# Genus_MainBoard_Lite-v_1_0.net
KiCad netlist of a schematic drawn in EAGLE
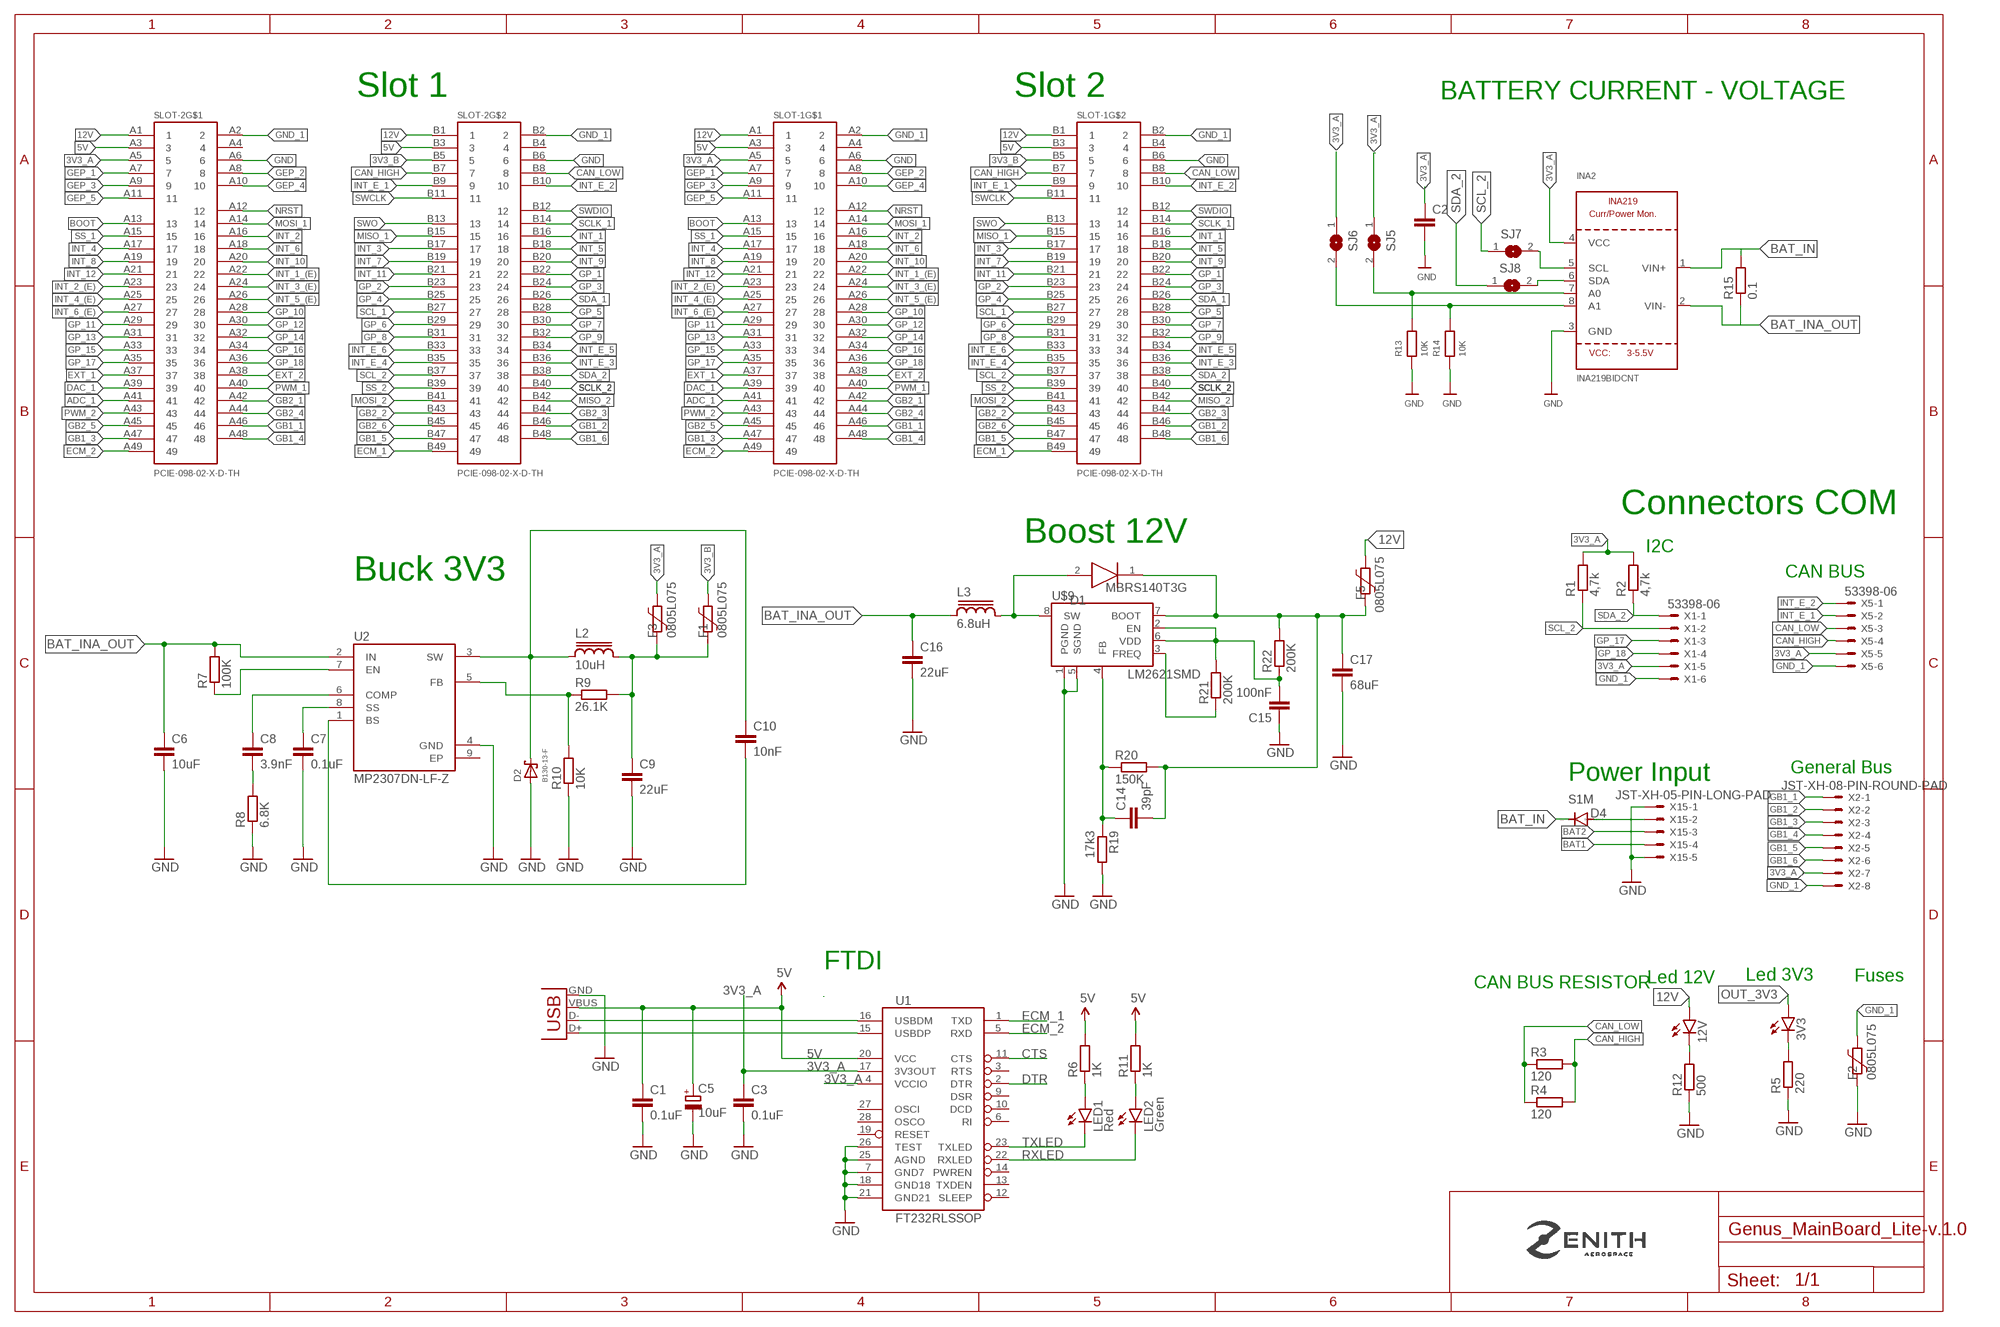
[diagram p0: schematic, sheet 1]

(export (version "E")
  (design (tool "Eeschema 10.0.6"))
  (components
    (comp (ref "3V3")
      (value "LEDCHIP-LED0805")
      (footprint "eagle-import:CHIP-LED0805")
      (libsource (lib "eagle-import") (part "LEDCHIP-LED0805"))
    )
    (comp (ref "12V")
      (value "LEDCHIP-LED0805")
      (footprint "eagle-import:CHIP-LED0805")
      (libsource (lib "eagle-import") (part "LEDCHIP-LED0805"))
    )
    (comp (ref "C1")
      (value "0.1uF")
      (footprint "eagle-import:C0805")
      (libsource (lib "eagle-import") (part "C-EUC0805"))
    )
    (comp (ref "C2")
      (value "C-EUC0805")
      (footprint "eagle-import:C0805")
      (libsource (lib "eagle-import") (part "C-EUC0805"))
    )
    (comp (ref "C3")
      (value "0.1uF")
      (footprint "eagle-import:C0805")
      (libsource (lib "eagle-import") (part "C-EUC0805"))
    )
    (comp (ref "C5")
      (value "10uF")
      (footprint "eagle-import:PANASONIC_B")
      (libsource (lib "eagle-import") (part "CPOL-EUB"))
    )
    (comp (ref "C6")
      (value "10uF")
      (footprint "eagle-import:C0805")
      (libsource (lib "eagle-import") (part "C-EUC0805"))
    )
    (comp (ref "C7")
      (value "0.1uF")
      (footprint "eagle-import:C0805")
      (libsource (lib "eagle-import") (part "C-EUC0805"))
    )
    (comp (ref "C8")
      (value "3.9nF")
      (footprint "eagle-import:C0805")
      (libsource (lib "eagle-import") (part "C-EUC0805"))
    )
    (comp (ref "C9")
      (value "22uF")
      (footprint "eagle-import:C0805")
      (libsource (lib "eagle-import") (part "C-EUC0805"))
    )
    (comp (ref "C10")
      (value "10nF")
      (footprint "eagle-import:C0805")
      (libsource (lib "eagle-import") (part "C-EUC0805"))
    )
    (comp (ref "C14")
      (value "39pF")
      (footprint "eagle-import:C0805")
      (libsource (lib "eagle-import") (part "C-EUC0805"))
    )
    (comp (ref "C15")
      (value "100nF")
      (footprint "eagle-import:C0805")
      (libsource (lib "eagle-import") (part "C-EUC0805"))
    )
    (comp (ref "C16")
      (value "22uF")
      (footprint "eagle-import:C1210")
      (libsource (lib "eagle-import") (part "C-EUC1210"))
    )
    (comp (ref "C17")
      (value "68uF")
      (footprint "eagle-import:C1210")
      (libsource (lib "eagle-import") (part "C-EUC1210"))
    )
    (comp (ref "D1")
      (value "MBRS140T3G")
      (footprint "eagle-import:DIOM5436X247N")
      (fields (field (name "RS_PART_NUMBER") "5452074P"))
      (libsource (lib "eagle-import") (part "MBRS140T3G"))
    )
    (comp (ref "D2")
      (value "B130-13-F")
      (footprint "eagle-import:SMA")
      (fields (field (name "MF") "Multicomp"))
      (libsource (lib "eagle-import") (part "B130-13-F"))
    )
    (comp (ref "D4")
      (value "S1M")
      (footprint "eagle-import:SMA")
      (libsource (lib "eagle-import") (part "S1M"))
    )
    (comp (ref "F1")
      (value "0805L075")
      (footprint "eagle-import:0805L")
      (fields (field (name "MF") "Littelfuse"))
      (libsource (lib "eagle-import") (part "?0805L075"))
    )
    (comp (ref "F2")
      (value "0805L075")
      (footprint "eagle-import:0805L")
      (fields (field (name "MF") "Littelfuse"))
      (libsource (lib "eagle-import") (part "?0805L075"))
    )
    (comp (ref "F3")
      (value "0805L075")
      (footprint "eagle-import:0805L")
      (fields (field (name "MF") "Littelfuse"))
      (libsource (lib "eagle-import") (part "?0805L075"))
    )
    (comp (ref "F5")
      (value "0805L075")
      (footprint "eagle-import:0805L")
      (fields (field (name "MF") "Littelfuse"))
      (libsource (lib "eagle-import") (part "?0805L075"))
    )
    (comp (ref "INA2")
      (value "INA219BIDCNT")
      (footprint "eagle-import:SOT23-8")
      (libsource (lib "eagle-import") (part "INA219"))
    )
    (comp (ref "L2")
      (value "10uH")
      (footprint "eagle-import:SRR1280")
      (libsource (lib "eagle-import") (part "SRR1280"))
    )
    (comp (ref "L3")
      (value "6.8uH")
      (footprint "eagle-import:SRR1280")
      (libsource (lib "eagle-import") (part "SRR1280"))
    )
    (comp (ref "LED1")
      (value "Red")
      (footprint "eagle-import:CHIPLED_0805")
      (libsource (lib "eagle-import") (part "LEDCHIPLED_0805"))
    )
    (comp (ref "LED2")
      (value "Green")
      (footprint "eagle-import:CHIPLED_0805")
      (libsource (lib "eagle-import") (part "LEDCHIPLED_0805"))
    )
    (comp (ref "R1")
      (value "4,7k")
      (footprint "eagle-import:R0805")
      (libsource (lib "eagle-import") (part "R-EU_R0805"))
    )
    (comp (ref "R2")
      (value "4,7k")
      (footprint "eagle-import:R0805")
      (libsource (lib "eagle-import") (part "R-EU_R0805"))
    )
    (comp (ref "R3")
      (value "120")
      (footprint "eagle-import:R0805")
      (libsource (lib "eagle-import") (part "R-EU_R0805"))
    )
    (comp (ref "R4")
      (value "120")
      (footprint "eagle-import:R0805")
      (libsource (lib "eagle-import") (part "R-EU_R0805"))
    )
    (comp (ref "R5")
      (value "220")
      (footprint "eagle-import:R0805")
      (libsource (lib "eagle-import") (part "R-EU_R0805"))
    )
    (comp (ref "R6")
      (value "1K")
      (footprint "eagle-import:R0805")
      (libsource (lib "eagle-import") (part "R-EU_R0805"))
    )
    (comp (ref "R7")
      (value "100K")
      (footprint "eagle-import:R0805")
      (libsource (lib "eagle-import") (part "R-EU_R0805"))
    )
    (comp (ref "R8")
      (value "6.8K")
      (footprint "eagle-import:R0805")
      (libsource (lib "eagle-import") (part "R-EU_R0805"))
    )
    (comp (ref "R9")
      (value "26.1K")
      (footprint "eagle-import:R0805")
      (libsource (lib "eagle-import") (part "R-EU_R0805"))
    )
    (comp (ref "R10")
      (value "10K")
      (footprint "eagle-import:R0805")
      (libsource (lib "eagle-import") (part "R-EU_R0805"))
    )
    (comp (ref "R11")
      (value "1K")
      (footprint "eagle-import:R0805")
      (libsource (lib "eagle-import") (part "R-EU_R0805"))
    )
    (comp (ref "R12")
      (value "500")
      (footprint "eagle-import:R0805")
      (libsource (lib "eagle-import") (part "R-EU_R0805"))
    )
    (comp (ref "R13")
      (value "10K")
      (footprint "eagle-import:R0805")
      (libsource (lib "eagle-import") (part "R-EU_R0805"))
    )
    (comp (ref "R14")
      (value "10K")
      (footprint "eagle-import:R0805")
      (libsource (lib "eagle-import") (part "R-EU_R0805"))
    )
    (comp (ref "R15")
      (value "0.1")
      (footprint "eagle-import:R2512")
      (libsource (lib "eagle-import") (part "R-EU_R2512"))
    )
    (comp (ref "R19")
      (value "17k3")
      (footprint "eagle-import:R0805")
      (libsource (lib "eagle-import") (part "R-EU_R0805"))
    )
    (comp (ref "R20")
      (value "150K")
      (footprint "eagle-import:R0805")
      (libsource (lib "eagle-import") (part "R-EU_R0805"))
    )
    (comp (ref "R21")
      (value "200K")
      (footprint "eagle-import:R0805")
      (libsource (lib "eagle-import") (part "R-EU_R0805"))
    )
    (comp (ref "R22")
      (value "200K")
      (footprint "eagle-import:R0805")
      (libsource (lib "eagle-import") (part "R-EU_R0805"))
    )
    (comp (ref "SJ5")
      (value "SOLDERJUMPERREFLOW_NOPASTE")
      (footprint "eagle-import:SOLDERJUMPER_REFLOW_NOPASTE")
      (libsource (lib "eagle-import") (part "SOLDERJUMPERREFLOW_NOPASTE"))
    )
    (comp (ref "SJ6")
      (value "SOLDERJUMPERREFLOW_NOPASTE")
      (footprint "eagle-import:SOLDERJUMPER_REFLOW_NOPASTE")
      (libsource (lib "eagle-import") (part "SOLDERJUMPERREFLOW_NOPASTE"))
    )
    (comp (ref "SJ7")
      (value "SOLDERJUMPERREFLOW_NOPASTE")
      (footprint "eagle-import:SOLDERJUMPER_REFLOW_NOPASTE")
      (libsource (lib "eagle-import") (part "SOLDERJUMPERREFLOW_NOPASTE"))
    )
    (comp (ref "SJ8")
      (value "SOLDERJUMPERREFLOW_NOPASTE")
      (footprint "eagle-import:SOLDERJUMPER_REFLOW_NOPASTE")
      (libsource (lib "eagle-import") (part "SOLDERJUMPERREFLOW_NOPASTE"))
    )
    (comp (ref "SLOT-1")
      (value "PCIE-098-02-X-D-TH")
      (footprint "eagle-import:PCIE-098-02-X-D-TH")
      (fields (field (name "MF") "Samtec") (field (name "MP") "PCIE-098-02-F-D-TH"))
      (libsource (lib "eagle-import") (part "PCIE-098-02-X-D-TH"))
    )
    (comp (ref "SLOT-2")
      (value "PCIE-098-02-X-D-TH")
      (footprint "eagle-import:PCIE-098-02-X-D-TH")
      (fields (field (name "MF") "Samtec") (field (name "MP") "PCIE-098-02-F-D-TH"))
      (libsource (lib "eagle-import") (part "PCIE-098-02-X-D-TH"))
    )
    (comp (ref "U$9")
      (value "LM2621SMD")
      (footprint "eagle-import:MSOP-8")
      (libsource (lib "eagle-import") (part "LM2621SMD"))
    )
    (comp (ref "U1")
      (value "FT232RLSSOP")
      (footprint "eagle-import:SSOP28DB")
      (libsource (lib "eagle-import") (part "FT232RLSSOP"))
    )
    (comp (ref "U2")
      (value "MP2307DN-LF-Z")
      (footprint "eagle-import:SOIC127P600X170-9N")
      (fields (field (name "MF") "Monolithic Power"))
      (libsource (lib "eagle-import") (part "MP2307DN-LF-Z"))
    )
    (comp (ref "X1")
      (value "53398-06")
      (footprint "eagle-import:53398-06")
      (fields (field (name "MF") "MOLEX"))
      (libsource (lib "eagle-import") (part "53?-06398"))
    )
    (comp (ref "X2")
      (value "JST-XH-08-PIN-ROUND-PAD")
      (footprint "eagle-import:JST-XH-08-PACKAGE-ROUND-PAD")
      (libsource (lib "eagle-import") (part "JST-XH-08-PIN-ROUND-PAD"))
    )
    (comp (ref "X3")
      (value "USB-SMD-NS")
      (footprint "eagle-import:USB-MINIB-NOSTOP")
      (libsource (lib "eagle-import") (part "USB-SMD-NS"))
    )
    (comp (ref "X5")
      (value "53398-06")
      (footprint "eagle-import:53398-06")
      (fields (field (name "MF") "MOLEX"))
      (libsource (lib "eagle-import") (part "53?-06398"))
    )
    (comp (ref "X15")
      (value "JST-XH-05-PIN-LONG-PAD")
      (footprint "eagle-import:JST-XH-05-PACKAGE-LONG-PAD")
      (libsource (lib "eagle-import") (part "JST-XH-05-PIN-LONG-PAD"))
    )
  )
  (nets
    (net (code "1") (name "/CTS") (class "Default")
      (node (ref "U1") (pin "11") (pinfunction "CTS_11") (pintype "input"))
    )
    (net (code "2") (name "/DTR") (class "Default")
      (node (ref "U1") (pin "2") (pinfunction "DTR_2") (pintype "output"))
    )
    (net (code "3") (name "/EP") (class "Default")
      (node (ref "U2") (pin "9") (pinfunction "EP_9") (pintype "power_in"))
    )
    (net (code "4") (name "/RXLED") (class "Default")
      (node (ref "LED2") (pin "C") (pinfunction "C_C") (pintype "passive"))
      (node (ref "U1") (pin "22") (pinfunction "RXLED_22") (pintype "input"))
    )
    (net (code "5") (name "/TXLED") (class "Default")
      (node (ref "LED1") (pin "C") (pinfunction "C_C") (pintype "passive"))
      (node (ref "U1") (pin "23") (pinfunction "TXLED_23") (pintype "input"))
    )
    (net (code "6") (name "3V3_A") (class "Default")
      (node (ref "C2") (pin "1") (pinfunction "1_1") (pintype "passive"))
      (node (ref "C3") (pin "1") (pinfunction "1_1") (pintype "passive"))
      (node (ref "F3") (pin "1") (pinfunction "1_1") (pintype "passive"))
      (node (ref "INA2") (pin "4") (pinfunction "VCC_4") (pintype "bidirectional"))
      (node (ref "R1") (pin "2") (pinfunction "2_2") (pintype "passive"))
      (node (ref "R2") (pin "2") (pinfunction "2_2") (pintype "passive"))
      (node (ref "SJ5") (pin "1") (pinfunction "1_1") (pintype "passive"))
      (node (ref "SJ6") (pin "1") (pinfunction "1_1") (pintype "passive"))
      (node (ref "SLOT-1") (pin "A5") (pinfunction "5_A5") (pintype "bidirectional"))
      (node (ref "SLOT-2") (pin "A5") (pinfunction "5_A5") (pintype "bidirectional"))
      (node (ref "U1") (pin "17") (pinfunction "3V3OUT_17") (pintype "output"))
      (node (ref "U1") (pin "4") (pinfunction "VCCIO_4") (pintype "power_in"))
      (node (ref "X1") (pin "5") (pinfunction "S_5") (pintype "passive"))
      (node (ref "X2") (pin "7") (pinfunction "S_7") (pintype "passive"))
      (node (ref "X5") (pin "5") (pinfunction "S_5") (pintype "passive"))
    )
    (net (code "7") (name "3V3_B") (class "Default")
      (node (ref "F1") (pin "1") (pinfunction "1_1") (pintype "passive"))
      (node (ref "SLOT-1") (pin "B5") (pinfunction "5_B5") (pintype "bidirectional"))
      (node (ref "SLOT-2") (pin "B5") (pinfunction "5_B5") (pintype "bidirectional"))
    )
    (net (code "8") (name "5V") (class "Default")
      (node (ref "C1") (pin "1") (pinfunction "1_1") (pintype "passive"))
      (node (ref "C5") (pin "+") (pinfunction "+_+") (pintype "passive"))
      (node (ref "R11") (pin "2") (pinfunction "2_2") (pintype "passive"))
      (node (ref "R6") (pin "2") (pinfunction "2_2") (pintype "passive"))
      (node (ref "SLOT-1") (pin "A3") (pinfunction "3_A3") (pintype "bidirectional"))
      (node (ref "SLOT-1") (pin "B3") (pinfunction "3_B3") (pintype "bidirectional"))
      (node (ref "SLOT-2") (pin "A3") (pinfunction "3_A3") (pintype "bidirectional"))
      (node (ref "SLOT-2") (pin "B3") (pinfunction "3_B3") (pintype "bidirectional"))
      (node (ref "U1") (pin "20") (pinfunction "VCC_20") (pintype "power_in"))
      (node (ref "X3") (pin "VBUS") (pinfunction "VBUS_VBUS") (pintype "bidirectional"))
    )
    (net (code "9") (name "12V") (class "Default")
      (node (ref "12V") (pin "A") (pinfunction "A_A") (pintype "passive"))
      (node (ref "F5") (pin "1") (pinfunction "1_1") (pintype "passive"))
      (node (ref "SLOT-1") (pin "A1") (pinfunction "1_A1") (pintype "bidirectional"))
      (node (ref "SLOT-1") (pin "B1") (pinfunction "1_B1") (pintype "bidirectional"))
      (node (ref "SLOT-2") (pin "A1") (pinfunction "1_A1") (pintype "bidirectional"))
      (node (ref "SLOT-2") (pin "B1") (pinfunction "1_B1") (pintype "bidirectional"))
    )
    (net (code "10") (name "ADC_1") (class "Default")
      (node (ref "SLOT-1") (pin "A41") (pinfunction "41_A41") (pintype "bidirectional"))
      (node (ref "SLOT-2") (pin "A41") (pinfunction "41_A41") (pintype "bidirectional"))
    )
    (net (code "11") (name "BAT1") (class "Default")
      (node (ref "X15") (pin "4") (pinfunction "S_4") (pintype "passive"))
    )
    (net (code "12") (name "BAT2") (class "Default")
      (node (ref "X15") (pin "3") (pinfunction "S_3") (pintype "passive"))
    )
    (net (code "13") (name "BAT_IN") (class "Default")
      (node (ref "D4") (pin "C") (pinfunction "C_C") (pintype "passive"))
      (node (ref "INA2") (pin "1") (pinfunction "VIN+_1") (pintype "bidirectional"))
      (node (ref "R15") (pin "2") (pinfunction "2_2") (pintype "passive"))
    )
    (net (code "14") (name "BAT_INA_OUT") (class "Default")
      (node (ref "C16") (pin "1") (pinfunction "1_1") (pintype "passive"))
      (node (ref "C6") (pin "1") (pinfunction "1_1") (pintype "passive"))
      (node (ref "INA2") (pin "2") (pinfunction "VIN-_2") (pintype "bidirectional"))
      (node (ref "L3") (pin "1") (pinfunction "1_1") (pintype "passive"))
      (node (ref "R15") (pin "1") (pinfunction "1_1") (pintype "passive"))
      (node (ref "R7") (pin "2") (pinfunction "2_2") (pintype "passive"))
      (node (ref "U2") (pin "2") (pinfunction "IN_2") (pintype "input"))
    )
    (net (code "15") (name "BOOT") (class "Default")
      (node (ref "SLOT-1") (pin "A13") (pinfunction "13_A13") (pintype "bidirectional"))
      (node (ref "SLOT-2") (pin "A13") (pinfunction "13_A13") (pintype "bidirectional"))
    )
    (net (code "16") (name "CAN_HIGH") (class "Default")
      (node (ref "R3") (pin "2") (pinfunction "2_2") (pintype "passive"))
      (node (ref "R4") (pin "2") (pinfunction "2_2") (pintype "passive"))
      (node (ref "SLOT-1") (pin "B7") (pinfunction "7_B7") (pintype "bidirectional"))
      (node (ref "SLOT-2") (pin "B7") (pinfunction "7_B7") (pintype "bidirectional"))
      (node (ref "X5") (pin "4") (pinfunction "S_4") (pintype "passive"))
    )
    (net (code "17") (name "CAN_LOW") (class "Default")
      (node (ref "R3") (pin "1") (pinfunction "1_1") (pintype "passive"))
      (node (ref "R4") (pin "1") (pinfunction "1_1") (pintype "passive"))
      (node (ref "SLOT-1") (pin "B8") (pinfunction "8_B8") (pintype "bidirectional"))
      (node (ref "SLOT-2") (pin "B8") (pinfunction "8_B8") (pintype "bidirectional"))
      (node (ref "X5") (pin "3") (pinfunction "S_3") (pintype "passive"))
    )
    (net (code "18") (name "DAC_1") (class "Default")
      (node (ref "SLOT-1") (pin "A39") (pinfunction "39_A39") (pintype "bidirectional"))
      (node (ref "SLOT-2") (pin "A39") (pinfunction "39_A39") (pintype "bidirectional"))
    )
    (net (code "19") (name "ECM_1") (class "Default")
      (node (ref "SLOT-1") (pin "B49") (pinfunction "49_B49") (pintype "bidirectional"))
      (node (ref "SLOT-2") (pin "B49") (pinfunction "49_B49") (pintype "bidirectional"))
      (node (ref "U1") (pin "1") (pinfunction "TXD_1") (pintype "output"))
    )
    (net (code "20") (name "ECM_2") (class "Default")
      (node (ref "SLOT-1") (pin "A49") (pinfunction "49_A49") (pintype "bidirectional"))
      (node (ref "SLOT-2") (pin "A49") (pinfunction "49_A49") (pintype "bidirectional"))
      (node (ref "U1") (pin "5") (pinfunction "RXD_5") (pintype "input"))
    )
    (net (code "21") (name "EXT_1") (class "Default")
      (node (ref "SLOT-1") (pin "A37") (pinfunction "37_A37") (pintype "bidirectional"))
      (node (ref "SLOT-2") (pin "A37") (pinfunction "37_A37") (pintype "bidirectional"))
    )
    (net (code "22") (name "EXT_2") (class "Default")
      (node (ref "SLOT-1") (pin "A38") (pinfunction "38_A38") (pintype "bidirectional"))
      (node (ref "SLOT-2") (pin "A38") (pinfunction "38_A38") (pintype "bidirectional"))
    )
    (net (code "23") (name "GB1_1") (class "Default")
      (node (ref "SLOT-1") (pin "A46") (pinfunction "46_A46") (pintype "bidirectional"))
      (node (ref "SLOT-2") (pin "A46") (pinfunction "46_A46") (pintype "bidirectional"))
      (node (ref "X2") (pin "1") (pinfunction "S_1") (pintype "passive"))
    )
    (net (code "24") (name "GB1_2") (class "Default")
      (node (ref "SLOT-1") (pin "B46") (pinfunction "46_B46") (pintype "bidirectional"))
      (node (ref "SLOT-2") (pin "B46") (pinfunction "46_B46") (pintype "bidirectional"))
      (node (ref "X2") (pin "2") (pinfunction "S_2") (pintype "passive"))
    )
    (net (code "25") (name "GB1_3") (class "Default")
      (node (ref "SLOT-1") (pin "A47") (pinfunction "47_A47") (pintype "bidirectional"))
      (node (ref "SLOT-2") (pin "A47") (pinfunction "47_A47") (pintype "bidirectional"))
      (node (ref "X2") (pin "3") (pinfunction "S_3") (pintype "passive"))
    )
    (net (code "26") (name "GB1_4") (class "Default")
      (node (ref "SLOT-1") (pin "A48") (pinfunction "48_A48") (pintype "bidirectional"))
      (node (ref "SLOT-2") (pin "A48") (pinfunction "48_A48") (pintype "bidirectional"))
      (node (ref "X2") (pin "4") (pinfunction "S_4") (pintype "passive"))
    )
    (net (code "27") (name "GB1_5") (class "Default")
      (node (ref "SLOT-1") (pin "B47") (pinfunction "47_B47") (pintype "bidirectional"))
      (node (ref "SLOT-2") (pin "B47") (pinfunction "47_B47") (pintype "bidirectional"))
      (node (ref "X2") (pin "5") (pinfunction "S_5") (pintype "passive"))
    )
    (net (code "28") (name "GB1_6") (class "Default")
      (node (ref "SLOT-1") (pin "B48") (pinfunction "48_B48") (pintype "bidirectional"))
      (node (ref "SLOT-2") (pin "B48") (pinfunction "48_B48") (pintype "bidirectional"))
      (node (ref "X2") (pin "6") (pinfunction "S_6") (pintype "passive"))
    )
    (net (code "29") (name "GB2_1") (class "Default")
      (node (ref "SLOT-1") (pin "A42") (pinfunction "42_A42") (pintype "bidirectional"))
      (node (ref "SLOT-2") (pin "A42") (pinfunction "42_A42") (pintype "bidirectional"))
    )
    (net (code "30") (name "GB2_2") (class "Default")
      (node (ref "SLOT-1") (pin "B43") (pinfunction "43_B43") (pintype "bidirectional"))
      (node (ref "SLOT-2") (pin "B43") (pinfunction "43_B43") (pintype "bidirectional"))
    )
    (net (code "31") (name "GB2_3") (class "Default")
      (node (ref "SLOT-1") (pin "B44") (pinfunction "44_B44") (pintype "bidirectional"))
      (node (ref "SLOT-2") (pin "B44") (pinfunction "44_B44") (pintype "bidirectional"))
    )
    (net (code "32") (name "GB2_4") (class "Default")
      (node (ref "SLOT-1") (pin "A44") (pinfunction "44_A44") (pintype "bidirectional"))
      (node (ref "SLOT-2") (pin "A44") (pinfunction "44_A44") (pintype "bidirectional"))
    )
    (net (code "33") (name "GB2_5") (class "Default")
      (node (ref "SLOT-1") (pin "A45") (pinfunction "45_A45") (pintype "bidirectional"))
      (node (ref "SLOT-2") (pin "A45") (pinfunction "45_A45") (pintype "bidirectional"))
    )
    (net (code "34") (name "GB2_6") (class "Default")
      (node (ref "SLOT-1") (pin "B45") (pinfunction "45_B45") (pintype "bidirectional"))
      (node (ref "SLOT-2") (pin "B45") (pinfunction "45_B45") (pintype "bidirectional"))
    )
    (net (code "35") (name "GEP_1") (class "Default")
      (node (ref "SLOT-1") (pin "A7") (pinfunction "7_A7") (pintype "bidirectional"))
      (node (ref "SLOT-2") (pin "A7") (pinfunction "7_A7") (pintype "bidirectional"))
    )
    (net (code "36") (name "GEP_2") (class "Default")
      (node (ref "SLOT-1") (pin "A8") (pinfunction "8_A8") (pintype "bidirectional"))
      (node (ref "SLOT-2") (pin "A8") (pinfunction "8_A8") (pintype "bidirectional"))
    )
    (net (code "37") (name "GEP_3") (class "Default")
      (node (ref "SLOT-1") (pin "A9") (pinfunction "9_A9") (pintype "bidirectional"))
      (node (ref "SLOT-2") (pin "A9") (pinfunction "9_A9") (pintype "bidirectional"))
    )
    (net (code "38") (name "GEP_4") (class "Default")
      (node (ref "SLOT-1") (pin "A10") (pinfunction "10_A10") (pintype "bidirectional"))
      (node (ref "SLOT-2") (pin "A10") (pinfunction "10_A10") (pintype "bidirectional"))
    )
    (net (code "39") (name "GEP_5") (class "Default")
      (node (ref "SLOT-1") (pin "A11") (pinfunction "11_A11") (pintype "bidirectional"))
      (node (ref "SLOT-2") (pin "A11") (pinfunction "11_A11") (pintype "bidirectional"))
    )
    (net (code "40") (name "GND") (class "Default")
      (node (ref "C1") (pin "2") (pinfunction "2_2") (pintype "passive"))
      (node (ref "C15") (pin "1") (pinfunction "1_1") (pintype "passive"))
      (node (ref "C16") (pin "2") (pinfunction "2_2") (pintype "passive"))
      (node (ref "C17") (pin "2") (pinfunction "2_2") (pintype "passive"))
      (node (ref "C2") (pin "2") (pinfunction "2_2") (pintype "passive"))
      (node (ref "C3") (pin "2") (pinfunction "2_2") (pintype "passive"))
      (node (ref "C5") (pin "-") (pinfunction "-_-") (pintype "passive"))
      (node (ref "C6") (pin "2") (pinfunction "2_2") (pintype "passive"))
      (node (ref "C7") (pin "2") (pinfunction "2_2") (pintype "passive"))
      (node (ref "C9") (pin "2") (pinfunction "2_2") (pintype "passive"))
      (node (ref "D2") (pin "A") (pinfunction "A_A") (pintype "passive"))
      (node (ref "F2") (pin "2") (pinfunction "2_2") (pintype "passive"))
      (node (ref "INA2") (pin "3") (pinfunction "GND_3") (pintype "bidirectional"))
      (node (ref "R10") (pin "1") (pinfunction "1_1") (pintype "passive"))
      (node (ref "R12") (pin "1") (pinfunction "1_1") (pintype "passive"))
      (node (ref "R13") (pin "1") (pinfunction "1_1") (pintype "passive"))
      (node (ref "R14") (pin "1") (pinfunction "1_1") (pintype "passive"))
      (node (ref "R19") (pin "2") (pinfunction "2_2") (pintype "passive"))
      (node (ref "R5") (pin "1") (pinfunction "1_1") (pintype "passive"))
      (node (ref "R8") (pin "1") (pinfunction "1_1") (pintype "passive"))
      (node (ref "SLOT-1") (pin "A6") (pinfunction "6_A6") (pintype "bidirectional"))
      (node (ref "SLOT-1") (pin "B6") (pinfunction "6_B6") (pintype "bidirectional"))
      (node (ref "SLOT-2") (pin "A6") (pinfunction "6_A6") (pintype "bidirectional"))
      (node (ref "SLOT-2") (pin "B6") (pinfunction "6_B6") (pintype "bidirectional"))
      (node (ref "U$9") (pin "1") (pinfunction "PGND_1") (pintype "bidirectional"))
      (node (ref "U$9") (pin "5") (pinfunction "SGND_5") (pintype "bidirectional"))
      (node (ref "U1") (pin "18") (pinfunction "GND18_18") (pintype "power_in"))
      (node (ref "U1") (pin "21") (pinfunction "GND21_21") (pintype "power_in"))
      (node (ref "U1") (pin "25") (pinfunction "AGND_25") (pintype "power_in"))
      (node (ref "U1") (pin "26") (pinfunction "TEST_26") (pintype "input"))
      (node (ref "U1") (pin "7") (pinfunction "GND7_7") (pintype "power_in"))
      (node (ref "U2") (pin "4") (pinfunction "GND_4") (pintype "power_in"))
      (node (ref "X15") (pin "1") (pinfunction "S_1") (pintype "passive"))
      (node (ref "X15") (pin "5") (pinfunction "S_5") (pintype "passive"))
      (node (ref "X3") (pin "GND") (pinfunction "GND_GND") (pintype "bidirectional"))
    )
    (net (code "41") (name "GND_1") (class "Default")
      (node (ref "F2") (pin "1") (pinfunction "1_1") (pintype "passive"))
      (node (ref "SLOT-1") (pin "A2") (pinfunction "2_A2") (pintype "bidirectional"))
      (node (ref "SLOT-1") (pin "B2") (pinfunction "2_B2") (pintype "bidirectional"))
      (node (ref "SLOT-2") (pin "A2") (pinfunction "2_A2") (pintype "bidirectional"))
      (node (ref "SLOT-2") (pin "B2") (pinfunction "2_B2") (pintype "bidirectional"))
      (node (ref "X1") (pin "6") (pinfunction "S_6") (pintype "passive"))
      (node (ref "X2") (pin "8") (pinfunction "S_8") (pintype "passive"))
      (node (ref "X5") (pin "6") (pinfunction "S_6") (pintype "passive"))
    )
    (net (code "42") (name "GP_1") (class "Default")
      (node (ref "SLOT-1") (pin "B22") (pinfunction "22_B22") (pintype "bidirectional"))
      (node (ref "SLOT-2") (pin "B22") (pinfunction "22_B22") (pintype "bidirectional"))
    )
    (net (code "43") (name "GP_2") (class "Default")
      (node (ref "SLOT-1") (pin "B23") (pinfunction "23_B23") (pintype "bidirectional"))
      (node (ref "SLOT-2") (pin "B23") (pinfunction "23_B23") (pintype "bidirectional"))
    )
    (net (code "44") (name "GP_3") (class "Default")
      (node (ref "SLOT-1") (pin "B24") (pinfunction "24_B24") (pintype "bidirectional"))
      (node (ref "SLOT-2") (pin "B24") (pinfunction "24_B24") (pintype "bidirectional"))
    )
    (net (code "45") (name "GP_4") (class "Default")
      (node (ref "SLOT-1") (pin "B25") (pinfunction "25_B25") (pintype "bidirectional"))
      (node (ref "SLOT-2") (pin "B25") (pinfunction "25_B25") (pintype "bidirectional"))
    )
    (net (code "46") (name "GP_5") (class "Default")
      (node (ref "SLOT-1") (pin "B28") (pinfunction "28_B28") (pintype "bidirectional"))
      (node (ref "SLOT-2") (pin "B28") (pinfunction "28_B28") (pintype "bidirectional"))
    )
    (net (code "47") (name "GP_6") (class "Default")
      (node (ref "SLOT-1") (pin "B29") (pinfunction "29_B29") (pintype "bidirectional"))
      (node (ref "SLOT-2") (pin "B29") (pinfunction "29_B29") (pintype "bidirectional"))
    )
    (net (code "48") (name "GP_7") (class "Default")
      (node (ref "SLOT-1") (pin "B30") (pinfunction "30_B30") (pintype "bidirectional"))
      (node (ref "SLOT-2") (pin "B30") (pinfunction "30_B30") (pintype "bidirectional"))
    )
    (net (code "49") (name "GP_8") (class "Default")
      (node (ref "SLOT-1") (pin "B31") (pinfunction "31_B31") (pintype "bidirectional"))
      (node (ref "SLOT-2") (pin "B31") (pinfunction "31_B31") (pintype "bidirectional"))
    )
    (net (code "50") (name "GP_9") (class "Default")
      (node (ref "SLOT-1") (pin "B32") (pinfunction "32_B32") (pintype "bidirectional"))
      (node (ref "SLOT-2") (pin "B32") (pinfunction "32_B32") (pintype "bidirectional"))
    )
    (net (code "51") (name "GP_10") (class "Default")
      (node (ref "SLOT-1") (pin "A28") (pinfunction "28_A28") (pintype "bidirectional"))
      (node (ref "SLOT-2") (pin "A28") (pinfunction "28_A28") (pintype "bidirectional"))
    )
    (net (code "52") (name "GP_11") (class "Default")
      (node (ref "SLOT-1") (pin "A29") (pinfunction "29_A29") (pintype "bidirectional"))
      (node (ref "SLOT-2") (pin "A29") (pinfunction "29_A29") (pintype "bidirectional"))
    )
    (net (code "53") (name "GP_12") (class "Default")
      (node (ref "SLOT-1") (pin "A30") (pinfunction "30_A30") (pintype "bidirectional"))
      (node (ref "SLOT-2") (pin "A30") (pinfunction "30_A30") (pintype "bidirectional"))
    )
    (net (code "54") (name "GP_13") (class "Default")
      (node (ref "SLOT-1") (pin "A31") (pinfunction "31_A31") (pintype "bidirectional"))
      (node (ref "SLOT-2") (pin "A31") (pinfunction "31_A31") (pintype "bidirectional"))
    )
    (net (code "55") (name "GP_14") (class "Default")
      (node (ref "SLOT-1") (pin "A32") (pinfunction "32_A32") (pintype "bidirectional"))
      (node (ref "SLOT-2") (pin "A32") (pinfunction "32_A32") (pintype "bidirectional"))
    )
    (net (code "56") (name "GP_15") (class "Default")
      (node (ref "SLOT-1") (pin "A33") (pinfunction "33_A33") (pintype "bidirectional"))
      (node (ref "SLOT-2") (pin "A33") (pinfunction "33_A33") (pintype "bidirectional"))
    )
    (net (code "57") (name "GP_16") (class "Default")
      (node (ref "SLOT-1") (pin "A34") (pinfunction "34_A34") (pintype "bidirectional"))
      (node (ref "SLOT-2") (pin "A34") (pinfunction "34_A34") (pintype "bidirectional"))
    )
    (net (code "58") (name "GP_17") (class "Default")
      (node (ref "SLOT-1") (pin "A35") (pinfunction "35_A35") (pintype "bidirectional"))
      (node (ref "SLOT-2") (pin "A35") (pinfunction "35_A35") (pintype "bidirectional"))
      (node (ref "X1") (pin "3") (pinfunction "S_3") (pintype "passive"))
    )
    (net (code "59") (name "GP_18") (class "Default")
      (node (ref "SLOT-1") (pin "A36") (pinfunction "36_A36") (pintype "bidirectional"))
      (node (ref "SLOT-2") (pin "A36") (pinfunction "36_A36") (pintype "bidirectional"))
      (node (ref "X1") (pin "4") (pinfunction "S_4") (pintype "passive"))
    )
    (net (code "60") (name "INT_1") (class "Default")
      (node (ref "SLOT-1") (pin "B16") (pinfunction "16_B16") (pintype "bidirectional"))
      (node (ref "SLOT-2") (pin "B16") (pinfunction "16_B16") (pintype "bidirectional"))
    )
    (net (code "61") (name "INT_1_(E)") (class "Default")
      (node (ref "SLOT-1") (pin "A22") (pinfunction "22_A22") (pintype "bidirectional"))
      (node (ref "SLOT-2") (pin "A22") (pinfunction "22_A22") (pintype "bidirectional"))
    )
    (net (code "62") (name "INT_2") (class "Default")
      (node (ref "SLOT-1") (pin "A16") (pinfunction "16_A16") (pintype "bidirectional"))
      (node (ref "SLOT-2") (pin "A16") (pinfunction "16_A16") (pintype "bidirectional"))
    )
    (net (code "63") (name "INT_2_(E)") (class "Default")
      (node (ref "SLOT-1") (pin "A23") (pinfunction "23_A23") (pintype "bidirectional"))
      (node (ref "SLOT-2") (pin "A23") (pinfunction "23_A23") (pintype "bidirectional"))
    )
    (net (code "64") (name "INT_3") (class "Default")
      (node (ref "SLOT-1") (pin "B17") (pinfunction "17_B17") (pintype "bidirectional"))
      (node (ref "SLOT-2") (pin "B17") (pinfunction "17_B17") (pintype "bidirectional"))
    )
    (net (code "65") (name "INT_3_(E)") (class "Default")
      (node (ref "SLOT-1") (pin "A24") (pinfunction "24_A24") (pintype "bidirectional"))
      (node (ref "SLOT-2") (pin "A24") (pinfunction "24_A24") (pintype "bidirectional"))
    )
    (net (code "66") (name "INT_4") (class "Default")
      (node (ref "SLOT-1") (pin "A17") (pinfunction "17_A17") (pintype "bidirectional"))
      (node (ref "SLOT-2") (pin "A17") (pinfunction "17_A17") (pintype "bidirectional"))
    )
    (net (code "67") (name "INT_4_(E)") (class "Default")
      (node (ref "SLOT-1") (pin "A25") (pinfunction "25_A25") (pintype "bidirectional"))
      (node (ref "SLOT-2") (pin "A25") (pinfunction "25_A25") (pintype "bidirectional"))
    )
    (net (code "68") (name "INT_5") (class "Default")
      (node (ref "SLOT-1") (pin "B18") (pinfunction "18_B18") (pintype "bidirectional"))
      (node (ref "SLOT-2") (pin "B18") (pinfunction "18_B18") (pintype "bidirectional"))
    )
    (net (code "69") (name "INT_5_(E)") (class "Default")
      (node (ref "SLOT-1") (pin "A26") (pinfunction "26_A26") (pintype "bidirectional"))
      (node (ref "SLOT-2") (pin "A26") (pinfunction "26_A26") (pintype "bidirectional"))
    )
    (net (code "70") (name "INT_6") (class "Default")
      (node (ref "SLOT-1") (pin "A18") (pinfunction "18_A18") (pintype "bidirectional"))
      (node (ref "SLOT-2") (pin "A18") (pinfunction "18_A18") (pintype "bidirectional"))
    )
    (net (code "71") (name "INT_6_(E)") (class "Default")
      (node (ref "SLOT-1") (pin "A27") (pinfunction "27_A27") (pintype "bidirectional"))
      (node (ref "SLOT-2") (pin "A27") (pinfunction "27_A27") (pintype "bidirectional"))
    )
    (net (code "72") (name "INT_7") (class "Default")
      (node (ref "SLOT-1") (pin "B19") (pinfunction "19_B19") (pintype "bidirectional"))
      (node (ref "SLOT-2") (pin "B19") (pinfunction "19_B19") (pintype "bidirectional"))
    )
    (net (code "73") (name "INT_8") (class "Default")
      (node (ref "SLOT-1") (pin "A19") (pinfunction "19_A19") (pintype "bidirectional"))
      (node (ref "SLOT-2") (pin "A19") (pinfunction "19_A19") (pintype "bidirectional"))
    )
    (net (code "74") (name "INT_9") (class "Default")
      (node (ref "SLOT-1") (pin "B20") (pinfunction "20_B20") (pintype "bidirectional"))
      (node (ref "SLOT-2") (pin "B20") (pinfunction "20_B20") (pintype "bidirectional"))
    )
    (net (code "75") (name "INT_10") (class "Default")
      (node (ref "SLOT-1") (pin "A20") (pinfunction "20_A20") (pintype "bidirectional"))
      (node (ref "SLOT-2") (pin "A20") (pinfunction "20_A20") (pintype "bidirectional"))
    )
    (net (code "76") (name "INT_11") (class "Default")
      (node (ref "SLOT-1") (pin "B21") (pinfunction "21_B21") (pintype "bidirectional"))
      (node (ref "SLOT-2") (pin "B21") (pinfunction "21_B21") (pintype "bidirectional"))
    )
    (net (code "77") (name "INT_12") (class "Default")
      (node (ref "SLOT-1") (pin "A21") (pinfunction "21_A21") (pintype "bidirectional"))
      (node (ref "SLOT-2") (pin "A21") (pinfunction "21_A21") (pintype "bidirectional"))
    )
    (net (code "78") (name "INT_E_1") (class "Default")
      (node (ref "SLOT-1") (pin "B9") (pinfunction "9_B9") (pintype "bidirectional"))
      (node (ref "SLOT-2") (pin "B9") (pinfunction "9_B9") (pintype "bidirectional"))
      (node (ref "X5") (pin "2") (pinfunction "S_2") (pintype "passive"))
    )
    (net (code "79") (name "INT_E_2") (class "Default")
      (node (ref "SLOT-1") (pin "B10") (pinfunction "10_B10") (pintype "bidirectional"))
      (node (ref "SLOT-2") (pin "B10") (pinfunction "10_B10") (pintype "bidirectional"))
      (node (ref "X5") (pin "1") (pinfunction "S_1") (pintype "passive"))
    )
    (net (code "80") (name "INT_E_3") (class "Default")
      (node (ref "SLOT-1") (pin "B36") (pinfunction "36_B36") (pintype "bidirectional"))
      (node (ref "SLOT-2") (pin "B36") (pinfunction "36_B36") (pintype "bidirectional"))
    )
    (net (code "81") (name "INT_E_4") (class "Default")
      (node (ref "SLOT-1") (pin "B35") (pinfunction "35_B35") (pintype "bidirectional"))
      (node (ref "SLOT-2") (pin "B35") (pinfunction "35_B35") (pintype "bidirectional"))
    )
    (net (code "82") (name "INT_E_5") (class "Default")
      (node (ref "SLOT-1") (pin "B34") (pinfunction "34_B34") (pintype "bidirectional"))
      (node (ref "SLOT-2") (pin "B34") (pinfunction "34_B34") (pintype "bidirectional"))
    )
    (net (code "83") (name "INT_E_6") (class "Default")
      (node (ref "SLOT-1") (pin "B33") (pinfunction "33_B33") (pintype "bidirectional"))
      (node (ref "SLOT-2") (pin "B33") (pinfunction "33_B33") (pintype "bidirectional"))
    )
    (net (code "84") (name "MISO_1") (class "Default")
      (node (ref "SLOT-1") (pin "B15") (pinfunction "15_B15") (pintype "bidirectional"))
      (node (ref "SLOT-2") (pin "B15") (pinfunction "15_B15") (pintype "bidirectional"))
    )
    (net (code "85") (name "MISO_2") (class "Default")
      (node (ref "SLOT-1") (pin "B42") (pinfunction "42_B42") (pintype "bidirectional"))
      (node (ref "SLOT-2") (pin "B42") (pinfunction "42_B42") (pintype "bidirectional"))
    )
    (net (code "86") (name "MOSI_1") (class "Default")
      (node (ref "SLOT-1") (pin "A14") (pinfunction "14_A14") (pintype "bidirectional"))
      (node (ref "SLOT-2") (pin "A14") (pinfunction "14_A14") (pintype "bidirectional"))
    )
    (net (code "87") (name "MOSI_2") (class "Default")
      (node (ref "SLOT-1") (pin "B41") (pinfunction "41_B41") (pintype "bidirectional"))
      (node (ref "SLOT-2") (pin "B41") (pinfunction "41_B41") (pintype "bidirectional"))
    )
    (net (code "88") (name "NRST") (class "Default")
      (node (ref "SLOT-1") (pin "A12") (pinfunction "12_A12") (pintype "bidirectional"))
      (node (ref "SLOT-2") (pin "A12") (pinfunction "12_A12") (pintype "bidirectional"))
    )
    (net (code "89") (name "Net-(3V3-PadC)") (class "Default")
      (node (ref "3V3") (pin "C") (pinfunction "C_C") (pintype "passive"))
      (node (ref "R5") (pin "2") (pinfunction "2_2") (pintype "passive"))
    )
    (net (code "90") (name "Net-(12V-PadC)") (class "Default")
      (node (ref "12V") (pin "C") (pinfunction "C_C") (pintype "passive"))
      (node (ref "R12") (pin "2") (pinfunction "2_2") (pintype "passive"))
    )
    (net (code "91") (name "Net-(C8-Pad2)") (class "Default")
      (node (ref "C8") (pin "2") (pinfunction "2_2") (pintype "passive"))
      (node (ref "R8") (pin "2") (pinfunction "2_2") (pintype "passive"))
    )
    (net (code "92") (name "Net-(D1-A)") (class "Default")
      (node (ref "D1") (pin "2") (pinfunction "A_2") (pintype "bidirectional"))
      (node (ref "L3") (pin "2") (pinfunction "2_2") (pintype "passive"))
      (node (ref "U$9") (pin "8") (pinfunction "SW_8") (pintype "bidirectional"))
    )
    (net (code "93") (name "Net-(D1-K)") (class "Default")
      (node (ref "C14") (pin "2") (pinfunction "2_2") (pintype "passive"))
      (node (ref "C17") (pin "1") (pinfunction "1_1") (pintype "passive"))
      (node (ref "D1") (pin "1") (pinfunction "K_1") (pintype "bidirectional"))
      (node (ref "F5") (pin "2") (pinfunction "2_2") (pintype "passive"))
      (node (ref "R20") (pin "2") (pinfunction "2_2") (pintype "passive"))
      (node (ref "R22") (pin "2") (pinfunction "2_2") (pintype "passive"))
      (node (ref "U$9") (pin "7") (pinfunction "BOOT_7") (pintype "bidirectional"))
    )
    (net (code "94") (name "Net-(INA2-A0)") (class "Default")
      (node (ref "INA2") (pin "7") (pinfunction "A0_7") (pintype "bidirectional"))
      (node (ref "R13") (pin "2") (pinfunction "2_2") (pintype "passive"))
      (node (ref "SJ5") (pin "2") (pinfunction "2_2") (pintype "passive"))
    )
    (net (code "95") (name "Net-(INA2-A1)") (class "Default")
      (node (ref "INA2") (pin "8") (pinfunction "A1_8") (pintype "bidirectional"))
      (node (ref "R14") (pin "2") (pinfunction "2_2") (pintype "passive"))
      (node (ref "SJ6") (pin "2") (pinfunction "2_2") (pintype "passive"))
    )
    (net (code "96") (name "Net-(INA2-SCL)") (class "Default")
      (node (ref "INA2") (pin "5") (pinfunction "SCL_5") (pintype "bidirectional"))
      (node (ref "SJ7") (pin "2") (pinfunction "2_2") (pintype "passive"))
    )
    (net (code "97") (name "Net-(INA2-SDA)") (class "Default")
      (node (ref "INA2") (pin "6") (pinfunction "SDA_6") (pintype "bidirectional"))
      (node (ref "SJ8") (pin "2") (pinfunction "2_2") (pintype "passive"))
    )
    (net (code "98") (name "Net-(LED1-PadA)") (class "Default")
      (node (ref "LED1") (pin "A") (pinfunction "A_A") (pintype "passive"))
      (node (ref "R6") (pin "1") (pinfunction "1_1") (pintype "passive"))
    )
    (net (code "99") (name "Net-(LED2-PadA)") (class "Default")
      (node (ref "LED2") (pin "A") (pinfunction "A_A") (pintype "passive"))
      (node (ref "R11") (pin "1") (pinfunction "1_1") (pintype "passive"))
    )
    (net (code "100") (name "Net-(U$9-EN)") (class "Default")
      (node (ref "C15") (pin "2") (pinfunction "2_2") (pintype "passive"))
      (node (ref "R21") (pin "2") (pinfunction "2_2") (pintype "passive"))
      (node (ref "R22") (pin "1") (pinfunction "1_1") (pintype "passive"))
      (node (ref "U$9") (pin "2") (pinfunction "EN_2") (pintype "bidirectional"))
      (node (ref "U$9") (pin "6") (pinfunction "VDD_6") (pintype "bidirectional"))
    )
    (net (code "101") (name "Net-(U$9-FB)") (class "Default")
      (node (ref "C14") (pin "1") (pinfunction "1_1") (pintype "passive"))
      (node (ref "R19") (pin "1") (pinfunction "1_1") (pintype "passive"))
      (node (ref "R20") (pin "1") (pinfunction "1_1") (pintype "passive"))
      (node (ref "U$9") (pin "4") (pinfunction "FB_4") (pintype "bidirectional"))
    )
    (net (code "102") (name "Net-(U$9-FREQ)") (class "Default")
      (node (ref "R21") (pin "1") (pinfunction "1_1") (pintype "passive"))
      (node (ref "U$9") (pin "3") (pinfunction "FREQ_3") (pintype "bidirectional"))
    )
    (net (code "103") (name "Net-(U1-USBDM)") (class "Default")
      (node (ref "U1") (pin "16") (pinfunction "USBDM_16") (pintype "bidirectional"))
      (node (ref "X3") (pin "D-") (pinfunction "D-_D-") (pintype "bidirectional"))
    )
    (net (code "104") (name "Net-(U1-USBDP)") (class "Default")
      (node (ref "U1") (pin "15") (pinfunction "USBDP_15") (pintype "bidirectional"))
      (node (ref "X3") (pin "D+") (pinfunction "D+_D+") (pintype "bidirectional"))
    )
    (net (code "105") (name "Net-(U2-BS)") (class "Default")
      (node (ref "C10") (pin "2") (pinfunction "2_2") (pintype "passive"))
      (node (ref "U2") (pin "1") (pinfunction "BS_1") (pintype "passive"))
    )
    (net (code "106") (name "Net-(U2-COMP)") (class "Default")
      (node (ref "C8") (pin "1") (pinfunction "1_1") (pintype "passive"))
      (node (ref "U2") (pin "6") (pinfunction "COMP_6") (pintype "passive"))
    )
    (net (code "107") (name "Net-(U2-EN)") (class "Default")
      (node (ref "R7") (pin "1") (pinfunction "1_1") (pintype "passive"))
      (node (ref "U2") (pin "7") (pinfunction "EN_7") (pintype "input"))
    )
    (net (code "108") (name "Net-(U2-FB)") (class "Default")
      (node (ref "R10") (pin "2") (pinfunction "2_2") (pintype "passive"))
      (node (ref "R9") (pin "1") (pinfunction "1_1") (pintype "passive"))
      (node (ref "U2") (pin "5") (pinfunction "FB_5") (pintype "input"))
    )
    (net (code "109") (name "Net-(U2-SS)") (class "Default")
      (node (ref "C7") (pin "1") (pinfunction "1_1") (pintype "passive"))
      (node (ref "U2") (pin "8") (pinfunction "SS_8") (pintype "passive"))
    )
    (net (code "110") (name "Net-(U2-SW)") (class "Default")
      (node (ref "C10") (pin "1") (pinfunction "1_1") (pintype "passive"))
      (node (ref "D2") (pin "C") (pinfunction "C_C") (pintype "passive"))
      (node (ref "L2") (pin "1") (pinfunction "1_1") (pintype "passive"))
      (node (ref "U2") (pin "3") (pinfunction "SW_3") (pintype "output"))
    )
    (net (code "111") (name "Net-(X15B-S)") (class "Default")
      (node (ref "D4") (pin "A") (pinfunction "A_A") (pintype "passive"))
      (node (ref "X15") (pin "2") (pinfunction "S_2") (pintype "passive"))
    )
    (net (code "112") (name "OUT_3V3") (class "Default")
      (node (ref "3V3") (pin "A") (pinfunction "A_A") (pintype "passive"))
      (node (ref "C9") (pin "1") (pinfunction "1_1") (pintype "passive"))
      (node (ref "F1") (pin "2") (pinfunction "2_2") (pintype "passive"))
      (node (ref "F3") (pin "2") (pinfunction "2_2") (pintype "passive"))
      (node (ref "L2") (pin "2") (pinfunction "2_2") (pintype "passive"))
      (node (ref "R9") (pin "2") (pinfunction "2_2") (pintype "passive"))
    )
    (net (code "113") (name "PWM_1") (class "Default")
      (node (ref "SLOT-1") (pin "A40") (pinfunction "40_A40") (pintype "bidirectional"))
      (node (ref "SLOT-2") (pin "A40") (pinfunction "40_A40") (pintype "bidirectional"))
    )
    (net (code "114") (name "PWM_2") (class "Default")
      (node (ref "SLOT-1") (pin "A43") (pinfunction "43_A43") (pintype "bidirectional"))
      (node (ref "SLOT-2") (pin "A43") (pinfunction "43_A43") (pintype "bidirectional"))
    )
    (net (code "115") (name "SCLK_1") (class "Default")
      (node (ref "SLOT-1") (pin "B14") (pinfunction "14_B14") (pintype "bidirectional"))
      (node (ref "SLOT-2") (pin "B14") (pinfunction "14_B14") (pintype "bidirectional"))
    )
    (net (code "116") (name "SCLK_2") (class "Default")
      (node (ref "SLOT-1") (pin "B40") (pinfunction "40_B40") (pintype "bidirectional"))
      (node (ref "SLOT-2") (pin "B40") (pinfunction "40_B40") (pintype "bidirectional"))
    )
    (net (code "117") (name "SCL_1") (class "Default")
      (node (ref "SLOT-1") (pin "B27") (pinfunction "27_B27") (pintype "bidirectional"))
      (node (ref "SLOT-2") (pin "B27") (pinfunction "27_B27") (pintype "bidirectional"))
    )
    (net (code "118") (name "SCL_2") (class "Default")
      (node (ref "R1") (pin "1") (pinfunction "1_1") (pintype "passive"))
      (node (ref "SJ7") (pin "1") (pinfunction "1_1") (pintype "passive"))
      (node (ref "SLOT-1") (pin "B37") (pinfunction "37_B37") (pintype "bidirectional"))
      (node (ref "SLOT-2") (pin "B37") (pinfunction "37_B37") (pintype "bidirectional"))
      (node (ref "X1") (pin "2") (pinfunction "S_2") (pintype "passive"))
    )
    (net (code "119") (name "SDA_1") (class "Default")
      (node (ref "SLOT-1") (pin "B26") (pinfunction "26_B26") (pintype "bidirectional"))
      (node (ref "SLOT-2") (pin "B26") (pinfunction "26_B26") (pintype "bidirectional"))
    )
    (net (code "120") (name "SDA_2") (class "Default")
      (node (ref "R2") (pin "1") (pinfunction "1_1") (pintype "passive"))
      (node (ref "SJ8") (pin "1") (pinfunction "1_1") (pintype "passive"))
      (node (ref "SLOT-1") (pin "B38") (pinfunction "38_B38") (pintype "bidirectional"))
      (node (ref "SLOT-2") (pin "B38") (pinfunction "38_B38") (pintype "bidirectional"))
      (node (ref "X1") (pin "1") (pinfunction "S_1") (pintype "passive"))
    )
    (net (code "121") (name "SS_1") (class "Default")
      (node (ref "SLOT-1") (pin "A15") (pinfunction "15_A15") (pintype "bidirectional"))
      (node (ref "SLOT-2") (pin "A15") (pinfunction "15_A15") (pintype "bidirectional"))
    )
    (net (code "122") (name "SS_2") (class "Default")
      (node (ref "SLOT-1") (pin "B39") (pinfunction "39_B39") (pintype "bidirectional"))
      (node (ref "SLOT-2") (pin "B39") (pinfunction "39_B39") (pintype "bidirectional"))
    )
    (net (code "123") (name "SWCLK") (class "Default")
      (node (ref "SLOT-1") (pin "B11") (pinfunction "11_B11") (pintype "bidirectional"))
      (node (ref "SLOT-2") (pin "B11") (pinfunction "11_B11") (pintype "bidirectional"))
    )
    (net (code "124") (name "SWDIO") (class "Default")
      (node (ref "SLOT-1") (pin "B12") (pinfunction "12_B12") (pintype "bidirectional"))
      (node (ref "SLOT-2") (pin "B12") (pinfunction "12_B12") (pintype "bidirectional"))
    )
    (net (code "125") (name "SWO") (class "Default")
      (node (ref "SLOT-1") (pin "B13") (pinfunction "13_B13") (pintype "bidirectional"))
      (node (ref "SLOT-2") (pin "B13") (pinfunction "13_B13") (pintype "bidirectional"))
    )
    (net (code "126") (name "unconnected-(SLOT-1A-4-PadA4)") (class "Default")
      (node (ref "SLOT-1") (pin "A4") (pinfunction "4_A4") (pintype "bidirectional"))
    )
    (net (code "127") (name "unconnected-(SLOT-1B-4-PadB4)") (class "Default")
      (node (ref "SLOT-1") (pin "B4") (pinfunction "4_B4") (pintype "bidirectional"))
    )
    (net (code "128") (name "unconnected-(SLOT-2A-4-PadA4)") (class "Default")
      (node (ref "SLOT-2") (pin "A4") (pinfunction "4_A4") (pintype "bidirectional"))
    )
    (net (code "129") (name "unconnected-(SLOT-2B-4-PadB4)") (class "Default")
      (node (ref "SLOT-2") (pin "B4") (pinfunction "4_B4") (pintype "bidirectional"))
    )
    (net (code "130") (name "unconnected-(U1-DCD-Pad10)") (class "Default")
      (node (ref "U1") (pin "10") (pinfunction "DCD_10") (pintype "input"))
    )
    (net (code "131") (name "unconnected-(U1-DSR-Pad9)") (class "Default")
      (node (ref "U1") (pin "9") (pinfunction "DSR_9") (pintype "input"))
    )
    (net (code "132") (name "unconnected-(U1-OSCI-Pad27)") (class "Default")
      (node (ref "U1") (pin "27") (pinfunction "OSCI_27") (pintype "input"))
    )
    (net (code "133") (name "unconnected-(U1-OSCO-Pad28)") (class "Default")
      (node (ref "U1") (pin "28") (pinfunction "OSCO_28") (pintype "output"))
    )
    (net (code "134") (name "unconnected-(U1-PWREN-Pad14)") (class "Default")
      (node (ref "U1") (pin "14") (pinfunction "PWREN_14") (pintype "input"))
    )
    (net (code "135") (name "unconnected-(U1-RESET-Pad19)") (class "Default")
      (node (ref "U1") (pin "19") (pinfunction "RESET_19") (pintype "input"))
    )
    (net (code "136") (name "unconnected-(U1-RI-Pad6)") (class "Default")
      (node (ref "U1") (pin "6") (pinfunction "RI_6") (pintype "input"))
    )
    (net (code "137") (name "unconnected-(U1-RTS-Pad3)") (class "Default")
      (node (ref "U1") (pin "3") (pinfunction "RTS_3") (pintype "output"))
    )
    (net (code "138") (name "unconnected-(U1-SLEEP-Pad12)") (class "Default")
      (node (ref "U1") (pin "12") (pinfunction "SLEEP_12") (pintype "input"))
    )
    (net (code "139") (name "unconnected-(U1-TXDEN-Pad13)") (class "Default")
      (node (ref "U1") (pin "13") (pinfunction "TXDEN_13") (pintype "input"))
    )
  )
)
